# SparkX_smol_Display.net
KiCad netlist of a schematic drawn in EAGLE
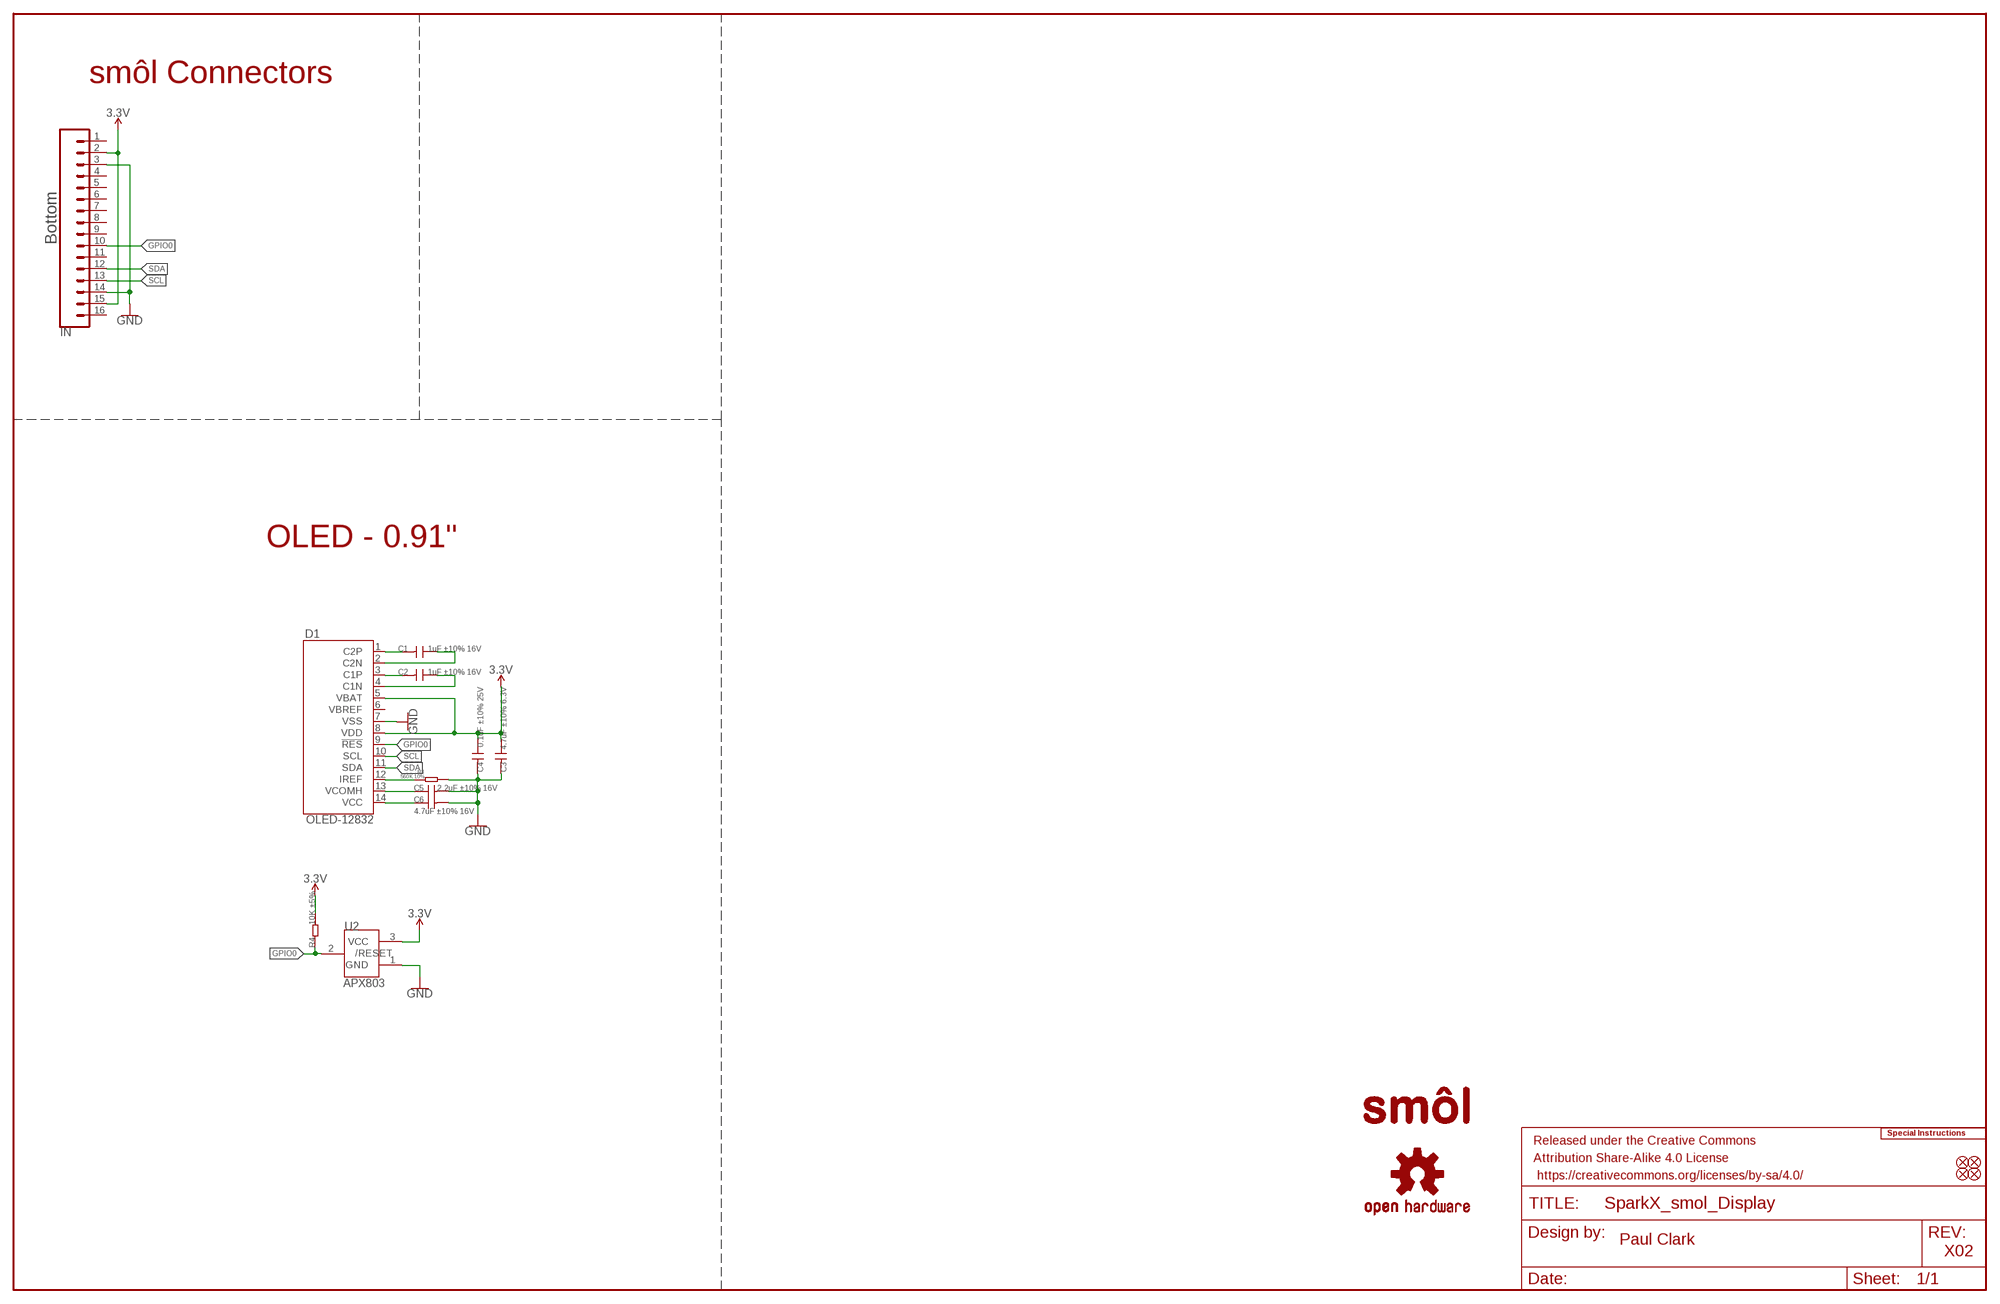
[diagram p0: schematic, sheet 1]

(export (version "E")
  (design (tool "Eeschema 10.0.6"))
  (components
    (comp (ref "C1")
      (value "1uF ±10% 16V")
      (footprint "eagle-import:0603")
      (libsource (lib "eagle-import") (part "C-0603"))
    )
    (comp (ref "C2")
      (value "1uF ±10% 16V")
      (footprint "eagle-import:0603")
      (libsource (lib "eagle-import") (part "C-0603"))
    )
    (comp (ref "C3")
      (value "4.7uF ±10% 6.3V")
      (footprint "eagle-import:0603")
      (libsource (lib "eagle-import") (part "C-0603"))
    )
    (comp (ref "C4")
      (value "0.1uF ±10% 25V")
      (footprint "eagle-import:0603")
      (libsource (lib "eagle-import") (part "C-0603"))
    )
    (comp (ref "C5")
      (value "2.2uF ±10% 16V")
      (footprint "eagle-import:0603")
      (libsource (lib "eagle-import") (part "C-0603"))
    )
    (comp (ref "C6")
      (value "4.7uF ±10% 16V")
      (footprint "eagle-import:0603")
      (libsource (lib "eagle-import") (part "C-0603"))
    )
    (comp (ref "D1")
      (value "OLED-12832")
      (footprint "eagle-import:OLED-12832")
      (libsource (lib "eagle-import") (part "OLED-12832"))
    )
    (comp (ref "FD1")
      (value "FIDUCIALUFIDUCIAL")
      (footprint "eagle-import:FIDUCIAL-MICRO")
      (libsource (lib "eagle-import") (part "FIDUCIALUFIDUCIAL"))
    )
    (comp (ref "FD2")
      (value "FIDUCIALUFIDUCIAL")
      (footprint "eagle-import:FIDUCIAL-MICRO")
      (libsource (lib "eagle-import") (part "FIDUCIALUFIDUCIAL"))
    )
    (comp (ref "FD3")
      (value "FIDUCIALUFIDUCIAL")
      (footprint "eagle-import:FIDUCIAL-MICRO")
      (libsource (lib "eagle-import") (part "FIDUCIALUFIDUCIAL"))
    )
    (comp (ref "FD4")
      (value "FIDUCIALUFIDUCIAL")
      (footprint "eagle-import:FIDUCIAL-MICRO")
      (libsource (lib "eagle-import") (part "FIDUCIALUFIDUCIAL"))
    )
    (comp (ref "FRAME1")
      (value "FRAME-LEDGER")
      (footprint "eagle-import:CREATIVE_COMMONS")
      (libsource (lib "eagle-import") (part "FRAME-LEDGER"))
    )
    (comp (ref "IN")
      (value "CONN_16FPC_16_0.5MM")
      (footprint "eagle-import:FPC_16_0.5MM")
      (libsource (lib "eagle-import") (part "CONN_16FPC_16_0.5MM"))
    )
    (comp (ref "LOGO1")
      (value "SPECIAL_INSTRUCTIONS-ORDERING")
      (footprint "eagle-import:ORDERING_INSTRUCTIONS")
      (libsource (lib "eagle-import") (part "SPECIAL_INSTRUCTIONS-ORDERING"))
    )
    (comp (ref "LOGO3")
      (value "OSHW-LOGOMINI")
      (footprint "eagle-import:OSHW-LOGO-MINI")
      (libsource (lib "eagle-import") (part "OSHW-LOGOMINI"))
    )
    (comp (ref "R3")
      (value "560K 10%")
      (footprint "eagle-import:0603")
      (libsource (lib "eagle-import") (part "R-0603"))
    )
    (comp (ref "R4")
      (value "10K ±5%")
      (footprint "eagle-import:0603")
      (libsource (lib "eagle-import") (part "R-0603"))
    )
    (comp (ref "U$14")
      (value "SMOL_LOGOSMALL")
      (footprint "eagle-import:SMOL_SMALL")
      (libsource (lib "eagle-import") (part "SMOL_LOGOSMALL"))
    )
    (comp (ref "U2")
      (value "APX803")
      (footprint "eagle-import:SOT23")
      (libsource (lib "eagle-import") (part "APX803"))
    )
  )
  (nets
    (net (code "1") (name "3.3V") (class "Default")
      (node (ref "C3") (pin "1") (pinfunction "1_1") (pintype "passive"))
      (node (ref "C4") (pin "1") (pinfunction "1_1") (pintype "passive"))
      (node (ref "D1") (pin "5") (pinfunction "VBAT_5") (pintype "bidirectional"))
      (node (ref "D1") (pin "8") (pinfunction "VDD_8") (pintype "bidirectional"))
      (node (ref "IN") (pin "15") (pinfunction "15_15") (pintype "passive"))
      (node (ref "IN") (pin "2") (pinfunction "2_2") (pintype "passive"))
      (node (ref "R4") (pin "2") (pinfunction "2_2") (pintype "passive"))
      (node (ref "U2") (pin "3") (pinfunction "VCC_3") (pintype "bidirectional"))
    )
    (net (code "2") (name "GND") (class "Default")
      (node (ref "C3") (pin "2") (pinfunction "2_2") (pintype "passive"))
      (node (ref "C4") (pin "2") (pinfunction "2_2") (pintype "passive"))
      (node (ref "C5") (pin "2") (pinfunction "2_2") (pintype "passive"))
      (node (ref "C6") (pin "2") (pinfunction "2_2") (pintype "passive"))
      (node (ref "D1") (pin "7") (pinfunction "VSS_7") (pintype "bidirectional"))
      (node (ref "IN") (pin "14") (pinfunction "14_14") (pintype "passive"))
      (node (ref "IN") (pin "3") (pinfunction "3_3") (pintype "passive"))
      (node (ref "R3") (pin "1") (pinfunction "1_1") (pintype "passive"))
      (node (ref "U2") (pin "1") (pinfunction "GND_1") (pintype "bidirectional"))
    )
    (net (code "3") (name "GPIO0") (class "Default")
      (node (ref "D1") (pin "9") (pinfunction "~{RES}_9") (pintype "bidirectional"))
      (node (ref "IN") (pin "10") (pinfunction "10_10") (pintype "passive"))
      (node (ref "R4") (pin "1") (pinfunction "1_1") (pintype "passive"))
      (node (ref "U2") (pin "2") (pinfunction "/RESET_2") (pintype "bidirectional"))
    )
    (net (code "4") (name "Net-(D1-C1N)") (class "Default")
      (node (ref "C2") (pin "1") (pinfunction "1_1") (pintype "passive"))
      (node (ref "D1") (pin "4") (pinfunction "C1N_4") (pintype "bidirectional"))
    )
    (net (code "5") (name "Net-(D1-C1P)") (class "Default")
      (node (ref "C2") (pin "2") (pinfunction "2_2") (pintype "passive"))
      (node (ref "D1") (pin "3") (pinfunction "C1P_3") (pintype "bidirectional"))
    )
    (net (code "6") (name "Net-(D1-C2N)") (class "Default")
      (node (ref "C1") (pin "1") (pinfunction "1_1") (pintype "passive"))
      (node (ref "D1") (pin "2") (pinfunction "C2N_2") (pintype "bidirectional"))
    )
    (net (code "7") (name "Net-(D1-C2P)") (class "Default")
      (node (ref "C1") (pin "2") (pinfunction "2_2") (pintype "passive"))
      (node (ref "D1") (pin "1") (pinfunction "C2P_1") (pintype "bidirectional"))
    )
    (net (code "8") (name "Net-(D1-IREF)") (class "Default")
      (node (ref "D1") (pin "12") (pinfunction "IREF_12") (pintype "bidirectional"))
      (node (ref "R3") (pin "2") (pinfunction "2_2") (pintype "passive"))
    )
    (net (code "9") (name "Net-(D1-VCC)") (class "Default")
      (node (ref "C6") (pin "1") (pinfunction "1_1") (pintype "passive"))
      (node (ref "D1") (pin "14") (pinfunction "VCC_14") (pintype "bidirectional"))
    )
    (net (code "10") (name "Net-(D1-VCOMH)") (class "Default")
      (node (ref "C5") (pin "1") (pinfunction "1_1") (pintype "passive"))
      (node (ref "D1") (pin "13") (pinfunction "VCOMH_13") (pintype "bidirectional"))
    )
    (net (code "11") (name "SCL") (class "Default")
      (node (ref "D1") (pin "10") (pinfunction "SCL_10") (pintype "bidirectional"))
      (node (ref "IN") (pin "13") (pinfunction "13_13") (pintype "passive"))
    )
    (net (code "12") (name "SDA") (class "Default")
      (node (ref "D1") (pin "11") (pinfunction "SDA_11") (pintype "bidirectional"))
      (node (ref "IN") (pin "12") (pinfunction "12_12") (pintype "passive"))
    )
    (net (code "13") (name "unconnected-(D1-VBREF-Pad6)") (class "Default")
      (node (ref "D1") (pin "6") (pinfunction "VBREF_6") (pintype "bidirectional"))
    )
    (net (code "14") (name "unconnected-(IN-Pad1)") (class "Default")
      (node (ref "IN") (pin "1") (pinfunction "1_1") (pintype "passive"))
    )
    (net (code "15") (name "unconnected-(IN-Pad4)") (class "Default")
      (node (ref "IN") (pin "4") (pinfunction "4_4") (pintype "passive"))
    )
    (net (code "16") (name "unconnected-(IN-Pad5)") (class "Default")
      (node (ref "IN") (pin "5") (pinfunction "5_5") (pintype "passive"))
    )
    (net (code "17") (name "unconnected-(IN-Pad6)") (class "Default")
      (node (ref "IN") (pin "6") (pinfunction "6_6") (pintype "passive"))
    )
    (net (code "18") (name "unconnected-(IN-Pad7)") (class "Default")
      (node (ref "IN") (pin "7") (pinfunction "7_7") (pintype "passive"))
    )
    (net (code "19") (name "unconnected-(IN-Pad8)") (class "Default")
      (node (ref "IN") (pin "8") (pinfunction "8_8") (pintype "passive"))
    )
    (net (code "20") (name "unconnected-(IN-Pad9)") (class "Default")
      (node (ref "IN") (pin "9") (pinfunction "9_9") (pintype "passive"))
    )
    (net (code "21") (name "unconnected-(IN-Pad11)") (class "Default")
      (node (ref "IN") (pin "11") (pinfunction "11_11") (pintype "passive"))
    )
    (net (code "22") (name "unconnected-(IN-Pad16)") (class "Default")
      (node (ref "IN") (pin "16") (pinfunction "16_16") (pintype "passive"))
    )
  )
)
